# ProDocument_Low_Cost_2023-07-23.net
KiCad netlist of a schematic drawn in EasyEDA Pro
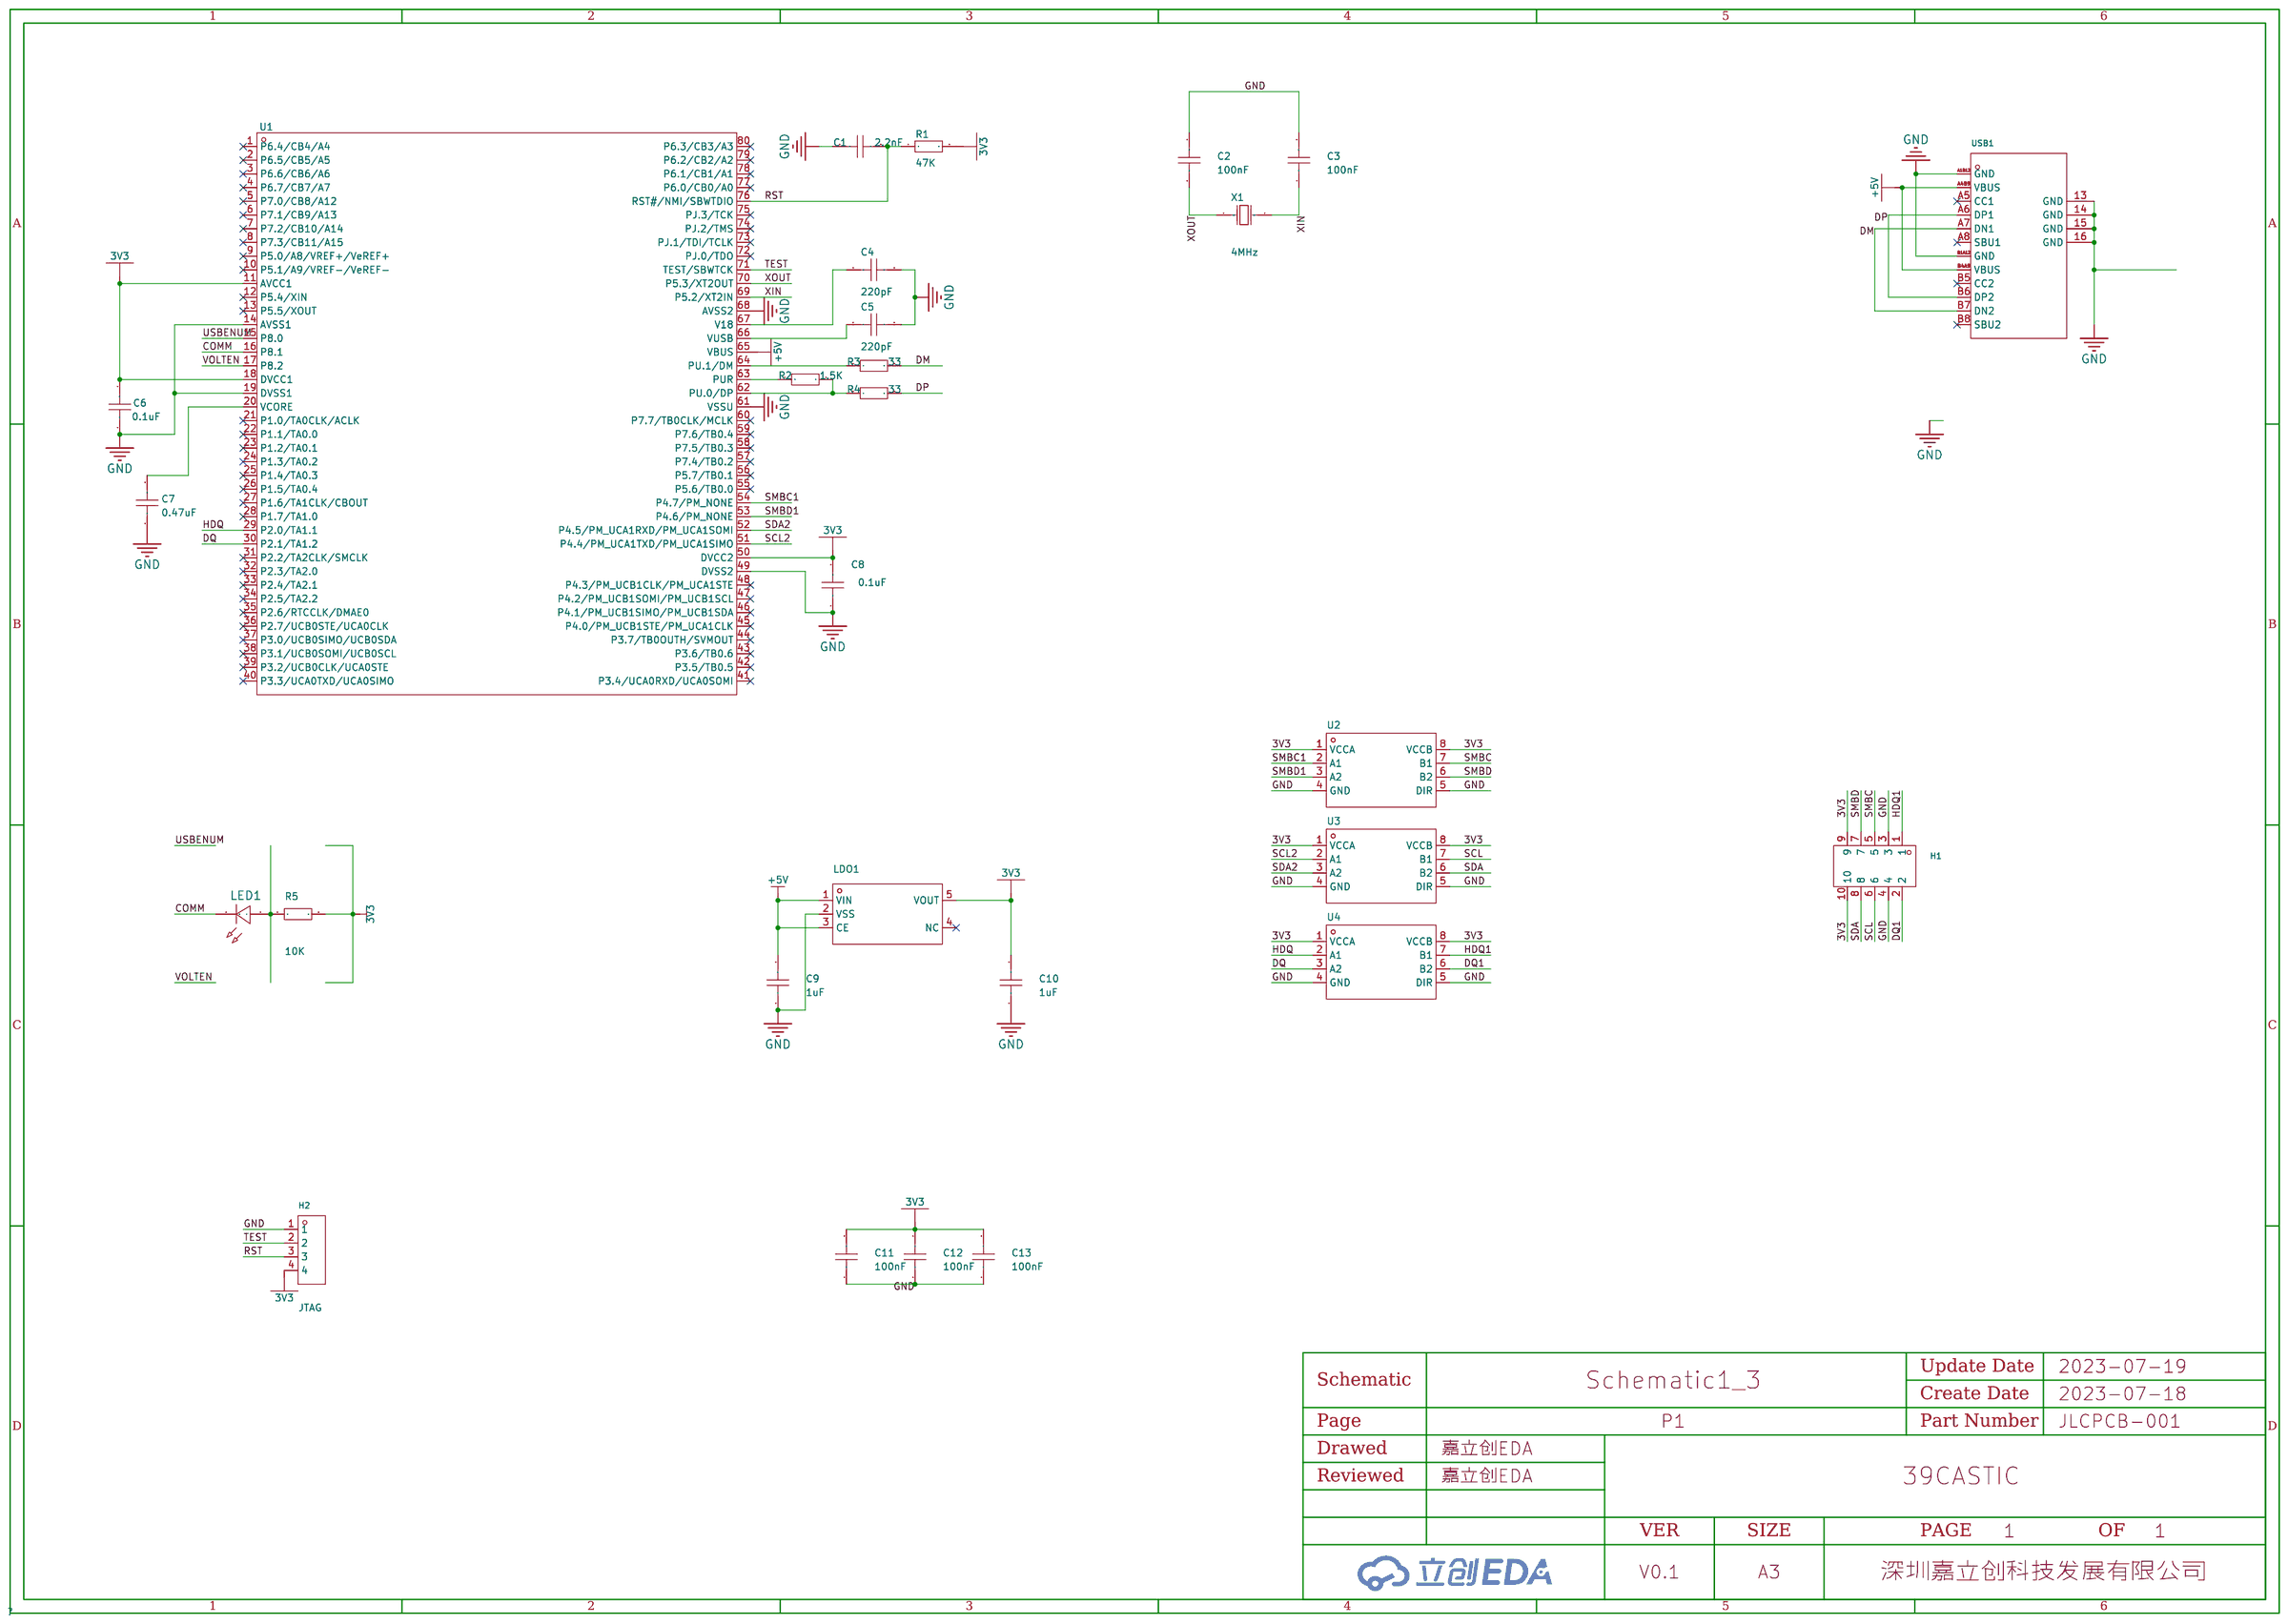
[diagram p0: schematic sheet]

(export (version "E")
  (design (tool "Eeschema 10.0.6"))
  (components
    (comp (ref "C1")
      (value "2.2nF")
      (footprint "easyedapro:C0603_1")
      (description "容值:100nF;精度:±10%;额定电压:50V;温度系数:X7R;")
      (libsource (lib "easyedapro") (part "C1210X7R475K630NT"))
    )
    (comp (ref "C2")
      (value "100nF")
      (footprint "easyedapro:C0603")
      (libsource (lib "easyedapro") (part "CapAcitance"))
    )
    (comp (ref "C3")
      (value "100nF")
      (footprint "easyedapro:C0603")
      (libsource (lib "easyedapro") (part "CapAcitance"))
    )
    (comp (ref "C4")
      (value "220pF")
      (footprint "easyedapro:C0603_1")
      (description "容值:100nF;精度:±10%;额定电压:50V;温度系数:X7R;")
      (libsource (lib "easyedapro") (part "C1210X7R475K630NT"))
    )
    (comp (ref "C5")
      (value "220pF")
      (footprint "easyedapro:C0603_1")
      (description "容值:100nF;精度:±10%;额定电压:50V;温度系数:X7R;")
      (libsource (lib "easyedapro") (part "C1210X7R475K630NT"))
    )
    (comp (ref "C6")
      (value "0.1uF")
      (footprint "easyedapro:C0603_1")
      (description "容值:100nF;精度:±10%;额定电压:50V;温度系数:X7R;")
      (libsource (lib "easyedapro") (part "C1210X7R475K630NT"))
    )
    (comp (ref "C7")
      (value "0.47uF")
      (footprint "easyedapro:C0603_1")
      (description "容值:100nF;精度:±10%;额定电压:50V;温度系数:X7R;")
      (libsource (lib "easyedapro") (part "C1210X7R475K630NT"))
    )
    (comp (ref "C8")
      (value "0.1uF")
      (footprint "easyedapro:C0603_1")
      (description "容值:100nF;精度:±10%;额定电压:50V;温度系数:X7R;")
      (libsource (lib "easyedapro") (part "C1210X7R475K630NT"))
    )
    (comp (ref "C9")
      (value "1uF")
      (footprint "easyedapro:C0603")
      (libsource (lib "easyedapro") (part "CapAcitance"))
    )
    (comp (ref "C10")
      (value "1uF")
      (footprint "easyedapro:C0603")
      (libsource (lib "easyedapro") (part "CapAcitance"))
    )
    (comp (ref "C11")
      (value "100nF")
      (footprint "easyedapro:C0603")
      (libsource (lib "easyedapro") (part "CapAcitance"))
    )
    (comp (ref "C12")
      (value "100nF")
      (footprint "easyedapro:C0603")
      (libsource (lib "easyedapro") (part "CapAcitance"))
    )
    (comp (ref "C13")
      (value "100nF")
      (footprint "easyedapro:C0603")
      (libsource (lib "easyedapro") (part "CapAcitance"))
    )
    (comp (ref "H1")
      (value "PZ254V-12-10P")
      (footprint "easyedapro:HDR-TH_10P-P2.54-V-M-R2-C5-S2.54")
      (fields (field (name "Manufacturer") "XFCN(兴飞)"))
      (libsource (lib "easyedapro") (part "PZ254V-12-10P"))
    )
    (comp (ref "H2")
      (value "JTAG")
      (footprint "easyedapro:HDR-TH_4P-P2.54-V-F")
      (libsource (lib "easyedapro") (part "2.54-1*4P母"))
    )
    (comp (ref "LDO1")
      (value "ME6211C33M5G-N")
      (footprint "easyedapro:SOT-23-5_L3.0-W1.7-P0.95-LS2.8-BL")
      (description "输出类型:固定;输出极性:正;最大输入电压:6V;输出电压:3.3V;输出电流:500mA;电源纹波抑制比(PSRR):70dB;")
      (fields (field (name "Manufacturer") "MICRONE(南京微盟)"))
      (libsource (lib "easyedapro") (part "ME6211C33M5G-N"))
    )
    (comp (ref "LED1")
      (value "~")
      (footprint "easyedapro:LED_0603")
      (libsource (lib "easyedapro") (part "LED_R"))
    )
    (comp (ref "R1")
      (value "47K")
      (footprint "easyedapro:R0603_1")
      (libsource (lib "easyedapro") (part "电阻_1"))
    )
    (comp (ref "R2")
      (value "1.5K")
      (footprint "easyedapro:R0603_1")
      (libsource (lib "easyedapro") (part "电阻_1"))
    )
    (comp (ref "R3")
      (value "33")
      (footprint "easyedapro:R0603_1")
      (libsource (lib "easyedapro") (part "电阻_1"))
    )
    (comp (ref "R4")
      (value "33")
      (footprint "easyedapro:R0603_1")
      (libsource (lib "easyedapro") (part "电阻_1"))
    )
    (comp (ref "R5") (value "10K") (footprint "easyedapro:R0603") (libsource (lib "easyedapro") (part "电阻")))
    (comp (ref "U1")
      (value "~")
      (footprint "easyedapro:LQFP-80_L12.0-W12.0-P0.50-LS14.0-BL")
      (description "CPU位数:-;ROM类型:-;CPU内核:-;主频（MAX):-;工作电压:-;")
      (fields (field (name "Manufacturer Part") "MSP430F5529IPN") (field (name "Manufacturer") "TI(德州仪器)"))
      (libsource (lib "easyedapro") (part "MSP430F5529IPN"))
    )
    (comp (ref "U2")
      (value "SN74LVC2T45DCUR")
      (footprint "easyedapro:VSSOP-8_L2.4-W2.1-P0.50-LS3.2-BR")
      (description "SN74LVC2T45 具有可配置电压转换和三态输出的 2 位双电源总线收发器")
      (fields (field (name "Manufacturer") "TI(德州仪器)"))
      (libsource (lib "easyedapro") (part "SN74LVC2T45DCUR"))
    )
    (comp (ref "U3")
      (value "SN74LVC2T45DCUR")
      (footprint "easyedapro:VSSOP-8_L2.4-W2.1-P0.50-LS3.2-BR")
      (description "SN74LVC2T45 具有可配置电压转换和三态输出的 2 位双电源总线收发器")
      (fields (field (name "Manufacturer") "TI(德州仪器)"))
      (libsource (lib "easyedapro") (part "SN74LVC2T45DCUR"))
    )
    (comp (ref "U4")
      (value "SN74LVC2T45DCUR")
      (footprint "easyedapro:VSSOP-8_L2.4-W2.1-P0.50-LS3.2-BR")
      (description "SN74LVC2T45 具有可配置电压转换和三态输出的 2 位双电源总线收发器")
      (fields (field (name "Manufacturer") "TI(德州仪器)"))
      (libsource (lib "easyedapro") (part "SN74LVC2T45DCUR"))
    )
    (comp (ref "USB1")
      (value "TYPEC-304-BCP16")
      (footprint "easyedapro:USB-C-SMD_TYPEC-304-BCP16")
      (fields (field (name "Manufacturer") "XUNPU(讯普)"))
      (libsource (lib "easyedapro") (part "TYPEC-304-BCP16"))
    )
    (comp (ref "X1")
      (value "4MHz")
      (footprint "easyedapro:HC-49US_L11.5-W4.5-P4.88")
      (description "频率:4MHz;频率公差:±20ppm;负载电容:20pF;")
      (fields (field (name "Manufacturer Part") "X49SD4MSD2SC") (field (name "Manufacturer") "YXC(扬兴晶振)"))
      (libsource (lib "easyedapro") (part "X49SD4MSD2SC"))
    )
  )
  (nets
    (net (code "1") (name "+5V") (class "Default")
      (node (ref "C9") (pin "2") (pinfunction "2_2") (pintype "input"))
      (node (ref "LDO1") (pin "1") (pinfunction "VIN_1") (pintype "input"))
      (node (ref "LDO1") (pin "3") (pinfunction "CE_3") (pintype "input"))
      (node (ref "U1") (pin "65") (pinfunction "VBUS_65") (pintype "input"))
      (node (ref "USB1") (pin "A4B9") (pinfunction "VBUS_A4B9") (pintype "input"))
      (node (ref "USB1") (pin "B4A9") (pinfunction "VBUS_B4A9") (pintype "input"))
    )
    (net (code "2") (name "/COMM") (class "Default")
      (node (ref "LED1") (pin "1") (pinfunction "C_1") (pintype "input"))
      (node (ref "U1") (pin "16") (pinfunction "P8.1_16") (pintype "input"))
    )
    (net (code "3") (name "/DM") (class "Default")
      (node (ref "R3") (pin "2") (pinfunction "2_2") (pintype "input"))
      (node (ref "USB1") (pin "A7") (pinfunction "DN1_A7") (pintype "input"))
      (node (ref "USB1") (pin "B7") (pinfunction "DN2_B7") (pintype "input"))
    )
    (net (code "4") (name "/DP") (class "Default")
      (node (ref "R4") (pin "2") (pinfunction "2_2") (pintype "input"))
      (node (ref "USB1") (pin "A6") (pinfunction "DP1_A6") (pintype "input"))
      (node (ref "USB1") (pin "B6") (pinfunction "DP2_B6") (pintype "input"))
    )
    (net (code "5") (name "/DQ") (class "Default")
      (node (ref "U1") (pin "30") (pinfunction "P2.1/TA1.2_30") (pintype "input"))
      (node (ref "U4") (pin "3") (pinfunction "A2_3") (pintype "input"))
    )
    (net (code "6") (name "/DQ1") (class "Default")
      (node (ref "H1") (pin "2") (pinfunction "2_2") (pintype "input"))
      (node (ref "U4") (pin "6") (pinfunction "B2_6") (pintype "input"))
    )
    (net (code "7") (name "/HDQ") (class "Default")
      (node (ref "U1") (pin "29") (pinfunction "P2.0/TA1.1_29") (pintype "input"))
      (node (ref "U4") (pin "2") (pinfunction "A1_2") (pintype "input"))
    )
    (net (code "8") (name "/HDQ1") (class "Default")
      (node (ref "H1") (pin "1") (pinfunction "1_1") (pintype "input"))
      (node (ref "U4") (pin "7") (pinfunction "B1_7") (pintype "input"))
    )
    (net (code "9") (name "/RST") (class "Default")
      (node (ref "C1") (pin "2") (pinfunction "2_2") (pintype "input"))
      (node (ref "H2") (pin "3") (pinfunction "3_3") (pintype "input"))
      (node (ref "R1") (pin "1") (pinfunction "1_1") (pintype "input"))
      (node (ref "U1") (pin "76") (pinfunction "RST#/NMI/SBWTDIO_76") (pintype "input"))
    )
    (net (code "10") (name "/SCL") (class "Default")
      (node (ref "H1") (pin "6") (pinfunction "6_6") (pintype "input"))
      (node (ref "U3") (pin "7") (pinfunction "B1_7") (pintype "input"))
    )
    (net (code "11") (name "/SCL2") (class "Default")
      (node (ref "U1") (pin "51") (pinfunction "P4.4/PM_UCA1TXD/PM_UCA1SIMO_51") (pintype "input"))
      (node (ref "U3") (pin "2") (pinfunction "A1_2") (pintype "input"))
    )
    (net (code "12") (name "/SDA") (class "Default")
      (node (ref "H1") (pin "8") (pinfunction "8_8") (pintype "input"))
      (node (ref "U3") (pin "6") (pinfunction "B2_6") (pintype "input"))
    )
    (net (code "13") (name "/SDA2") (class "Default")
      (node (ref "U1") (pin "52") (pinfunction "P4.5/PM_UCA1RXD/PM_UCA1SOMI_52") (pintype "input"))
      (node (ref "U3") (pin "3") (pinfunction "A2_3") (pintype "input"))
    )
    (net (code "14") (name "/SMBC") (class "Default")
      (node (ref "H1") (pin "5") (pinfunction "5_5") (pintype "input"))
      (node (ref "U2") (pin "7") (pinfunction "B1_7") (pintype "input"))
    )
    (net (code "15") (name "/SMBC1") (class "Default")
      (node (ref "U1") (pin "54") (pinfunction "P4.7/PM_NONE_54") (pintype "input"))
      (node (ref "U2") (pin "2") (pinfunction "A1_2") (pintype "input"))
    )
    (net (code "16") (name "/SMBD") (class "Default")
      (node (ref "H1") (pin "7") (pinfunction "7_7") (pintype "input"))
      (node (ref "U2") (pin "6") (pinfunction "B2_6") (pintype "input"))
    )
    (net (code "17") (name "/SMBD1") (class "Default")
      (node (ref "U1") (pin "53") (pinfunction "P4.6/PM_NONE_53") (pintype "input"))
      (node (ref "U2") (pin "3") (pinfunction "A2_3") (pintype "input"))
    )
    (net (code "18") (name "/TEST") (class "Default")
      (node (ref "H2") (pin "2") (pinfunction "2_2") (pintype "input"))
      (node (ref "U1") (pin "71") (pinfunction "TEST/SBWTCK_71") (pintype "input"))
    )
    (net (code "19") (name "/USBENUM") (class "Default")
      (node (ref "U1") (pin "15") (pinfunction "P8.0_15") (pintype "input"))
    )
    (net (code "20") (name "/VOLTEN") (class "Default")
      (node (ref "U1") (pin "17") (pinfunction "P8.2_17") (pintype "input"))
    )
    (net (code "21") (name "/XIN") (class "Default")
      (node (ref "C3") (pin "1") (pinfunction "1_1") (pintype "input"))
      (node (ref "U1") (pin "69") (pinfunction "P5.2/XT2IN_69") (pintype "input"))
      (node (ref "X1") (pin "1") (pinfunction "OSC1_1") (pintype "input"))
    )
    (net (code "22") (name "/XOUT") (class "Default")
      (node (ref "C2") (pin "1") (pinfunction "1_1") (pintype "input"))
      (node (ref "U1") (pin "70") (pinfunction "P5.3/XT2OUT_70") (pintype "input"))
      (node (ref "X1") (pin "2") (pinfunction "OSC2_2") (pintype "input"))
    )
    (net (code "23") (name "3V3") (class "Default")
      (node (ref "C10") (pin "2") (pinfunction "2_2") (pintype "input"))
      (node (ref "C11") (pin "2") (pinfunction "2_2") (pintype "input"))
      (node (ref "C12") (pin "2") (pinfunction "2_2") (pintype "input"))
      (node (ref "C13") (pin "2") (pinfunction "2_2") (pintype "input"))
      (node (ref "C6") (pin "2") (pinfunction "2_2") (pintype "input"))
      (node (ref "C8") (pin "2") (pinfunction "2_2") (pintype "input"))
      (node (ref "H1") (pin "10") (pinfunction "10_10") (pintype "input"))
      (node (ref "H1") (pin "9") (pinfunction "9_9") (pintype "input"))
      (node (ref "H2") (pin "4") (pinfunction "4_4") (pintype "input"))
      (node (ref "LDO1") (pin "5") (pinfunction "VOUT_5") (pintype "input"))
      (node (ref "R1") (pin "2") (pinfunction "2_2") (pintype "input"))
      (node (ref "R5") (pin "2") (pinfunction "2_2") (pintype "input"))
      (node (ref "U1") (pin "11") (pinfunction "AVCC1_11") (pintype "input"))
      (node (ref "U1") (pin "18") (pinfunction "DVCC1_18") (pintype "input"))
      (node (ref "U1") (pin "50") (pinfunction "DVCC2_50") (pintype "input"))
      (node (ref "U2") (pin "1") (pinfunction "VCCA_1") (pintype "input"))
      (node (ref "U2") (pin "8") (pinfunction "VCCB_8") (pintype "input"))
      (node (ref "U3") (pin "1") (pinfunction "VCCA_1") (pintype "input"))
      (node (ref "U3") (pin "8") (pinfunction "VCCB_8") (pintype "input"))
      (node (ref "U4") (pin "1") (pinfunction "VCCA_1") (pintype "input"))
      (node (ref "U4") (pin "8") (pinfunction "VCCB_8") (pintype "input"))
    )
    (net (code "24") (name "GND") (class "Default")
      (node (ref "C1") (pin "1") (pinfunction "1_1") (pintype "input"))
      (node (ref "C10") (pin "1") (pinfunction "1_1") (pintype "input"))
      (node (ref "C11") (pin "1") (pinfunction "1_1") (pintype "input"))
      (node (ref "C12") (pin "1") (pinfunction "1_1") (pintype "input"))
      (node (ref "C13") (pin "1") (pinfunction "1_1") (pintype "input"))
      (node (ref "C2") (pin "2") (pinfunction "2_2") (pintype "input"))
      (node (ref "C3") (pin "2") (pinfunction "2_2") (pintype "input"))
      (node (ref "C4") (pin "2") (pinfunction "2_2") (pintype "input"))
      (node (ref "C5") (pin "2") (pinfunction "2_2") (pintype "input"))
      (node (ref "C6") (pin "1") (pinfunction "1_1") (pintype "input"))
      (node (ref "C7") (pin "1") (pinfunction "1_1") (pintype "input"))
      (node (ref "C8") (pin "1") (pinfunction "1_1") (pintype "input"))
      (node (ref "C9") (pin "1") (pinfunction "1_1") (pintype "input"))
      (node (ref "H1") (pin "3") (pinfunction "3_3") (pintype "input"))
      (node (ref "H1") (pin "4") (pinfunction "4_4") (pintype "input"))
      (node (ref "H2") (pin "1") (pinfunction "1_1") (pintype "input"))
      (node (ref "LDO1") (pin "2") (pinfunction "VSS_2") (pintype "input"))
      (node (ref "U1") (pin "14") (pinfunction "AVSS1_14") (pintype "input"))
      (node (ref "U1") (pin "19") (pinfunction "DVSS1_19") (pintype "input"))
      (node (ref "U1") (pin "49") (pinfunction "DVSS2_49") (pintype "input"))
      (node (ref "U1") (pin "61") (pinfunction "VSSU_61") (pintype "input"))
      (node (ref "U1") (pin "68") (pinfunction "AVSS2_68") (pintype "input"))
      (node (ref "U2") (pin "4") (pinfunction "GND_4") (pintype "input"))
      (node (ref "U2") (pin "5") (pinfunction "DIR_5") (pintype "input"))
      (node (ref "U3") (pin "4") (pinfunction "GND_4") (pintype "input"))
      (node (ref "U3") (pin "5") (pinfunction "DIR_5") (pintype "input"))
      (node (ref "U4") (pin "4") (pinfunction "GND_4") (pintype "input"))
      (node (ref "U4") (pin "5") (pinfunction "DIR_5") (pintype "input"))
      (node (ref "USB1") (pin "13") (pinfunction "GND_13") (pintype "input"))
      (node (ref "USB1") (pin "14") (pinfunction "GND_14") (pintype "input"))
      (node (ref "USB1") (pin "15") (pinfunction "GND_15") (pintype "input"))
      (node (ref "USB1") (pin "16") (pinfunction "GND_16") (pintype "input"))
      (node (ref "USB1") (pin "A1B12") (pinfunction "GND_A1B12") (pintype "input"))
      (node (ref "USB1") (pin "B1A12") (pinfunction "GND_B1A12") (pintype "input"))
    )
    (net (code "25") (name "Net-(LED1-A)") (class "Default")
      (node (ref "LED1") (pin "2") (pinfunction "A_2") (pintype "input"))
      (node (ref "R5") (pin "1") (pinfunction "1_1") (pintype "input"))
    )
    (net (code "26") (name "Net-(U1-PU.0{slash}DP)") (class "Default")
      (node (ref "R2") (pin "2") (pinfunction "2_2") (pintype "input"))
      (node (ref "R4") (pin "1") (pinfunction "1_1") (pintype "input"))
      (node (ref "U1") (pin "62") (pinfunction "PU.0/DP_62") (pintype "input"))
    )
    (net (code "27") (name "Net-(U1-PU.1{slash}DM)") (class "Default")
      (node (ref "R3") (pin "1") (pinfunction "1_1") (pintype "input"))
      (node (ref "U1") (pin "64") (pinfunction "PU.1/DM_64") (pintype "input"))
    )
    (net (code "28") (name "Net-(U1-PUR)") (class "Default")
      (node (ref "R2") (pin "1") (pinfunction "1_1") (pintype "input"))
      (node (ref "U1") (pin "63") (pinfunction "PUR_63") (pintype "input"))
    )
    (net (code "29") (name "Net-(U1-V18)") (class "Default")
      (node (ref "C4") (pin "1") (pinfunction "1_1") (pintype "input"))
      (node (ref "U1") (pin "67") (pinfunction "V18_67") (pintype "input"))
    )
    (net (code "30") (name "Net-(U1-VCORE)") (class "Default")
      (node (ref "C7") (pin "2") (pinfunction "2_2") (pintype "input"))
      (node (ref "U1") (pin "20") (pinfunction "VCORE_20") (pintype "input"))
    )
    (net (code "31") (name "Net-(U1-VUSB)") (class "Default")
      (node (ref "C5") (pin "1") (pinfunction "1_1") (pintype "input"))
      (node (ref "U1") (pin "66") (pinfunction "VUSB_66") (pintype "input"))
    )
    (net (code "32") (name "unconnected-(LDO1-NC-Pad4)") (class "Default")
      (node (ref "LDO1") (pin "4") (pinfunction "NC_4") (pintype "input+no_connect"))
    )
    (net (code "33") (name "unconnected-(U1-P1.0{slash}TA0CLK{slash}ACLK-Pad21)") (class "Default")
      (node (ref "U1") (pin "21") (pinfunction "P1.0/TA0CLK/ACLK_21") (pintype "input+no_connect"))
    )
    (net (code "34") (name "unconnected-(U1-P1.1{slash}TA0.0-Pad22)") (class "Default")
      (node (ref "U1") (pin "22") (pinfunction "P1.1/TA0.0_22") (pintype "input+no_connect"))
    )
    (net (code "35") (name "unconnected-(U1-P1.2{slash}TA0.1-Pad23)") (class "Default")
      (node (ref "U1") (pin "23") (pinfunction "P1.2/TA0.1_23") (pintype "input+no_connect"))
    )
    (net (code "36") (name "unconnected-(U1-P1.3{slash}TA0.2-Pad24)") (class "Default")
      (node (ref "U1") (pin "24") (pinfunction "P1.3/TA0.2_24") (pintype "input+no_connect"))
    )
    (net (code "37") (name "unconnected-(U1-P1.4{slash}TA0.3-Pad25)") (class "Default")
      (node (ref "U1") (pin "25") (pinfunction "P1.4/TA0.3_25") (pintype "input+no_connect"))
    )
    (net (code "38") (name "unconnected-(U1-P1.5{slash}TA0.4-Pad26)") (class "Default")
      (node (ref "U1") (pin "26") (pinfunction "P1.5/TA0.4_26") (pintype "input+no_connect"))
    )
    (net (code "39") (name "unconnected-(U1-P1.6{slash}TA1CLK{slash}CBOUT-Pad27)") (class "Default")
      (node (ref "U1") (pin "27") (pinfunction "P1.6/TA1CLK/CBOUT_27") (pintype "input+no_connect"))
    )
    (net (code "40") (name "unconnected-(U1-P1.7{slash}TA1.0-Pad28)") (class "Default")
      (node (ref "U1") (pin "28") (pinfunction "P1.7/TA1.0_28") (pintype "input+no_connect"))
    )
    (net (code "41") (name "unconnected-(U1-P2.2{slash}TA2CLK{slash}SMCLK-Pad31)") (class "Default")
      (node (ref "U1") (pin "31") (pinfunction "P2.2/TA2CLK/SMCLK_31") (pintype "input+no_connect"))
    )
    (net (code "42") (name "unconnected-(U1-P2.3{slash}TA2.0-Pad32)") (class "Default")
      (node (ref "U1") (pin "32") (pinfunction "P2.3/TA2.0_32") (pintype "input+no_connect"))
    )
    (net (code "43") (name "unconnected-(U1-P2.4{slash}TA2.1-Pad33)") (class "Default")
      (node (ref "U1") (pin "33") (pinfunction "P2.4/TA2.1_33") (pintype "input+no_connect"))
    )
    (net (code "44") (name "unconnected-(U1-P2.5{slash}TA2.2-Pad34)") (class "Default")
      (node (ref "U1") (pin "34") (pinfunction "P2.5/TA2.2_34") (pintype "input+no_connect"))
    )
    (net (code "45") (name "unconnected-(U1-P2.6{slash}RTCCLK{slash}DMAE0-Pad35)") (class "Default")
      (node (ref "U1") (pin "35") (pinfunction "P2.6/RTCCLK/DMAE0_35") (pintype "input+no_connect"))
    )
    (net (code "46") (name "unconnected-(U1-P2.7{slash}UCB0STE{slash}UCA0CLK-Pad36)") (class "Default")
      (node (ref "U1") (pin "36") (pinfunction "P2.7/UCB0STE/UCA0CLK_36") (pintype "input+no_connect"))
    )
    (net (code "47") (name "unconnected-(U1-P3.0{slash}UCB0SIMO{slash}UCB0SDA-Pad37)") (class "Default")
      (node (ref "U1") (pin "37") (pinfunction "P3.0/UCB0SIMO/UCB0SDA_37") (pintype "input+no_connect"))
    )
    (net (code "48") (name "unconnected-(U1-P3.1{slash}UCB0SOMI{slash}UCB0SCL-Pad38)") (class "Default")
      (node (ref "U1") (pin "38") (pinfunction "P3.1/UCB0SOMI/UCB0SCL_38") (pintype "input+no_connect"))
    )
    (net (code "49") (name "unconnected-(U1-P3.2{slash}UCB0CLK{slash}UCA0STE-Pad39)") (class "Default")
      (node (ref "U1") (pin "39") (pinfunction "P3.2/UCB0CLK/UCA0STE_39") (pintype "input+no_connect"))
    )
    (net (code "50") (name "unconnected-(U1-P3.3{slash}UCA0TXD{slash}UCA0SIMO-Pad40)") (class "Default")
      (node (ref "U1") (pin "40") (pinfunction "P3.3/UCA0TXD/UCA0SIMO_40") (pintype "input+no_connect"))
    )
    (net (code "51") (name "unconnected-(U1-P3.4{slash}UCA0RXD{slash}UCA0SOMI-Pad41)") (class "Default")
      (node (ref "U1") (pin "41") (pinfunction "P3.4/UCA0RXD/UCA0SOMI_41") (pintype "input+no_connect"))
    )
    (net (code "52") (name "unconnected-(U1-P3.5{slash}TB0.5-Pad42)") (class "Default")
      (node (ref "U1") (pin "42") (pinfunction "P3.5/TB0.5_42") (pintype "input+no_connect"))
    )
    (net (code "53") (name "unconnected-(U1-P3.6{slash}TB0.6-Pad43)") (class "Default")
      (node (ref "U1") (pin "43") (pinfunction "P3.6/TB0.6_43") (pintype "input+no_connect"))
    )
    (net (code "54") (name "unconnected-(U1-P3.7{slash}TB0OUTH{slash}SVMOUT-Pad44)") (class "Default")
      (node (ref "U1") (pin "44") (pinfunction "P3.7/TB0OUTH/SVMOUT_44") (pintype "input+no_connect"))
    )
    (net (code "55") (name "unconnected-(U1-P4.0{slash}PM_UCB1STE{slash}PM_UCA1CLK-Pad45)") (class "Default")
      (node (ref "U1") (pin "45") (pinfunction "P4.0/PM_UCB1STE/PM_UCA1CLK_45") (pintype "input+no_connect"))
    )
    (net (code "56") (name "unconnected-(U1-P4.1{slash}PM_UCB1SIMO{slash}PM_UCB1SDA-Pad46)") (class "Default")
      (node (ref "U1") (pin "46") (pinfunction "P4.1/PM_UCB1SIMO/PM_UCB1SDA_46") (pintype "input+no_connect"))
    )
    (net (code "57") (name "unconnected-(U1-P4.2{slash}PM_UCB1SOMI{slash}PM_UCB1SCL-Pad47)") (class "Default")
      (node (ref "U1") (pin "47") (pinfunction "P4.2/PM_UCB1SOMI/PM_UCB1SCL_47") (pintype "input+no_connect"))
    )
    (net (code "58") (name "unconnected-(U1-P4.3{slash}PM_UCB1CLK{slash}PM_UCA1STE-Pad48)") (class "Default")
      (node (ref "U1") (pin "48") (pinfunction "P4.3/PM_UCB1CLK/PM_UCA1STE_48") (pintype "input+no_connect"))
    )
    (net (code "59") (name "unconnected-(U1-P5.0{slash}A8{slash}VREF+{slash}VeREF+-Pad9)") (class "Default")
      (node (ref "U1") (pin "9") (pinfunction "P5.0/A8/VREF+/VeREF+_9") (pintype "input+no_connect"))
    )
    (net (code "60") (name "unconnected-(U1-P5.1{slash}A9{slash}VREF-{slash}VeREF--Pad10)") (class "Default")
      (node (ref "U1") (pin "10") (pinfunction "P5.1/A9/VREF-/VeREF-_10") (pintype "input+no_connect"))
    )
    (net (code "61") (name "unconnected-(U1-P5.4{slash}XIN-Pad12)") (class "Default")
      (node (ref "U1") (pin "12") (pinfunction "P5.4/XIN_12") (pintype "input+no_connect"))
    )
    (net (code "62") (name "unconnected-(U1-P5.5{slash}XOUT-Pad13)") (class "Default")
      (node (ref "U1") (pin "13") (pinfunction "P5.5/XOUT_13") (pintype "input+no_connect"))
    )
    (net (code "63") (name "unconnected-(U1-P5.6{slash}TB0.0-Pad55)") (class "Default")
      (node (ref "U1") (pin "55") (pinfunction "P5.6/TB0.0_55") (pintype "input+no_connect"))
    )
    (net (code "64") (name "unconnected-(U1-P5.7{slash}TB0.1-Pad56)") (class "Default")
      (node (ref "U1") (pin "56") (pinfunction "P5.7/TB0.1_56") (pintype "input+no_connect"))
    )
    (net (code "65") (name "unconnected-(U1-P6.0{slash}CB0{slash}A0-Pad77)") (class "Default")
      (node (ref "U1") (pin "77") (pinfunction "P6.0/CB0/A0_77") (pintype "input+no_connect"))
    )
    (net (code "66") (name "unconnected-(U1-P6.1{slash}CB1{slash}A1-Pad78)") (class "Default")
      (node (ref "U1") (pin "78") (pinfunction "P6.1/CB1/A1_78") (pintype "input+no_connect"))
    )
    (net (code "67") (name "unconnected-(U1-P6.2{slash}CB2{slash}A2-Pad79)") (class "Default")
      (node (ref "U1") (pin "79") (pinfunction "P6.2/CB2/A2_79") (pintype "input+no_connect"))
    )
    (net (code "68") (name "unconnected-(U1-P6.3{slash}CB3{slash}A3-Pad80)") (class "Default")
      (node (ref "U1") (pin "80") (pinfunction "P6.3/CB3/A3_80") (pintype "input+no_connect"))
    )
    (net (code "69") (name "unconnected-(U1-P6.4{slash}CB4{slash}A4-Pad1)") (class "Default")
      (node (ref "U1") (pin "1") (pinfunction "P6.4/CB4/A4_1") (pintype "input+no_connect"))
    )
    (net (code "70") (name "unconnected-(U1-P6.5{slash}CB5{slash}A5-Pad2)") (class "Default")
      (node (ref "U1") (pin "2") (pinfunction "P6.5/CB5/A5_2") (pintype "input+no_connect"))
    )
    (net (code "71") (name "unconnected-(U1-P6.6{slash}CB6{slash}A6-Pad3)") (class "Default")
      (node (ref "U1") (pin "3") (pinfunction "P6.6/CB6/A6_3") (pintype "input+no_connect"))
    )
    (net (code "72") (name "unconnected-(U1-P6.7{slash}CB7{slash}A7-Pad4)") (class "Default")
      (node (ref "U1") (pin "4") (pinfunction "P6.7/CB7/A7_4") (pintype "input+no_connect"))
    )
    (net (code "73") (name "unconnected-(U1-P7.0{slash}CB8{slash}A12-Pad5)") (class "Default")
      (node (ref "U1") (pin "5") (pinfunction "P7.0/CB8/A12_5") (pintype "input+no_connect"))
    )
    (net (code "74") (name "unconnected-(U1-P7.1{slash}CB9{slash}A13-Pad6)") (class "Default")
      (node (ref "U1") (pin "6") (pinfunction "P7.1/CB9/A13_6") (pintype "input+no_connect"))
    )
    (net (code "75") (name "unconnected-(U1-P7.2{slash}CB10{slash}A14-Pad7)") (class "Default")
      (node (ref "U1") (pin "7") (pinfunction "P7.2/CB10/A14_7") (pintype "input+no_connect"))
    )
    (net (code "76") (name "unconnected-(U1-P7.3{slash}CB11{slash}A15-Pad8)") (class "Default")
      (node (ref "U1") (pin "8") (pinfunction "P7.3/CB11/A15_8") (pintype "input+no_connect"))
    )
    (net (code "77") (name "unconnected-(U1-P7.4{slash}TB0.2-Pad57)") (class "Default")
      (node (ref "U1") (pin "57") (pinfunction "P7.4/TB0.2_57") (pintype "input+no_connect"))
    )
    (net (code "78") (name "unconnected-(U1-P7.5{slash}TB0.3-Pad58)") (class "Default")
      (node (ref "U1") (pin "58") (pinfunction "P7.5/TB0.3_58") (pintype "input+no_connect"))
    )
    (net (code "79") (name "unconnected-(U1-P7.6{slash}TB0.4-Pad59)") (class "Default")
      (node (ref "U1") (pin "59") (pinfunction "P7.6/TB0.4_59") (pintype "input+no_connect"))
    )
    (net (code "80") (name "unconnected-(U1-P7.7{slash}TB0CLK{slash}MCLK-Pad60)") (class "Default")
      (node (ref "U1") (pin "60") (pinfunction "P7.7/TB0CLK/MCLK_60") (pintype "input+no_connect"))
    )
    (net (code "81") (name "unconnected-(U1-PJ.0{slash}TDO-Pad72)") (class "Default")
      (node (ref "U1") (pin "72") (pinfunction "PJ.0/TDO_72") (pintype "input+no_connect"))
    )
    (net (code "82") (name "unconnected-(U1-PJ.1{slash}TDI{slash}TCLK-Pad73)") (class "Default")
      (node (ref "U1") (pin "73") (pinfunction "PJ.1/TDI/TCLK_73") (pintype "input+no_connect"))
    )
    (net (code "83") (name "unconnected-(U1-PJ.2{slash}TMS-Pad74)") (class "Default")
      (node (ref "U1") (pin "74") (pinfunction "PJ.2/TMS_74") (pintype "input+no_connect"))
    )
    (net (code "84") (name "unconnected-(U1-PJ.3{slash}TCK-Pad75)") (class "Default")
      (node (ref "U1") (pin "75") (pinfunction "PJ.3/TCK_75") (pintype "input+no_connect"))
    )
    (net (code "85") (name "unconnected-(USB1-CC1-PadA5)") (class "Default")
      (node (ref "USB1") (pin "A5") (pinfunction "CC1_A5") (pintype "input+no_connect"))
    )
    (net (code "86") (name "unconnected-(USB1-CC2-PadB5)") (class "Default")
      (node (ref "USB1") (pin "B5") (pinfunction "CC2_B5") (pintype "input+no_connect"))
    )
    (net (code "87") (name "unconnected-(USB1-SBU1-PadA8)") (class "Default")
      (node (ref "USB1") (pin "A8") (pinfunction "SBU1_A8") (pintype "input+no_connect"))
    )
    (net (code "88") (name "unconnected-(USB1-SBU2-PadB8)") (class "Default")
      (node (ref "USB1") (pin "B8") (pinfunction "SBU2_B8") (pintype "input+no_connect"))
    )
  )
)
